# thick.net
KiCad netlist of a schematic drawn in EAGLE
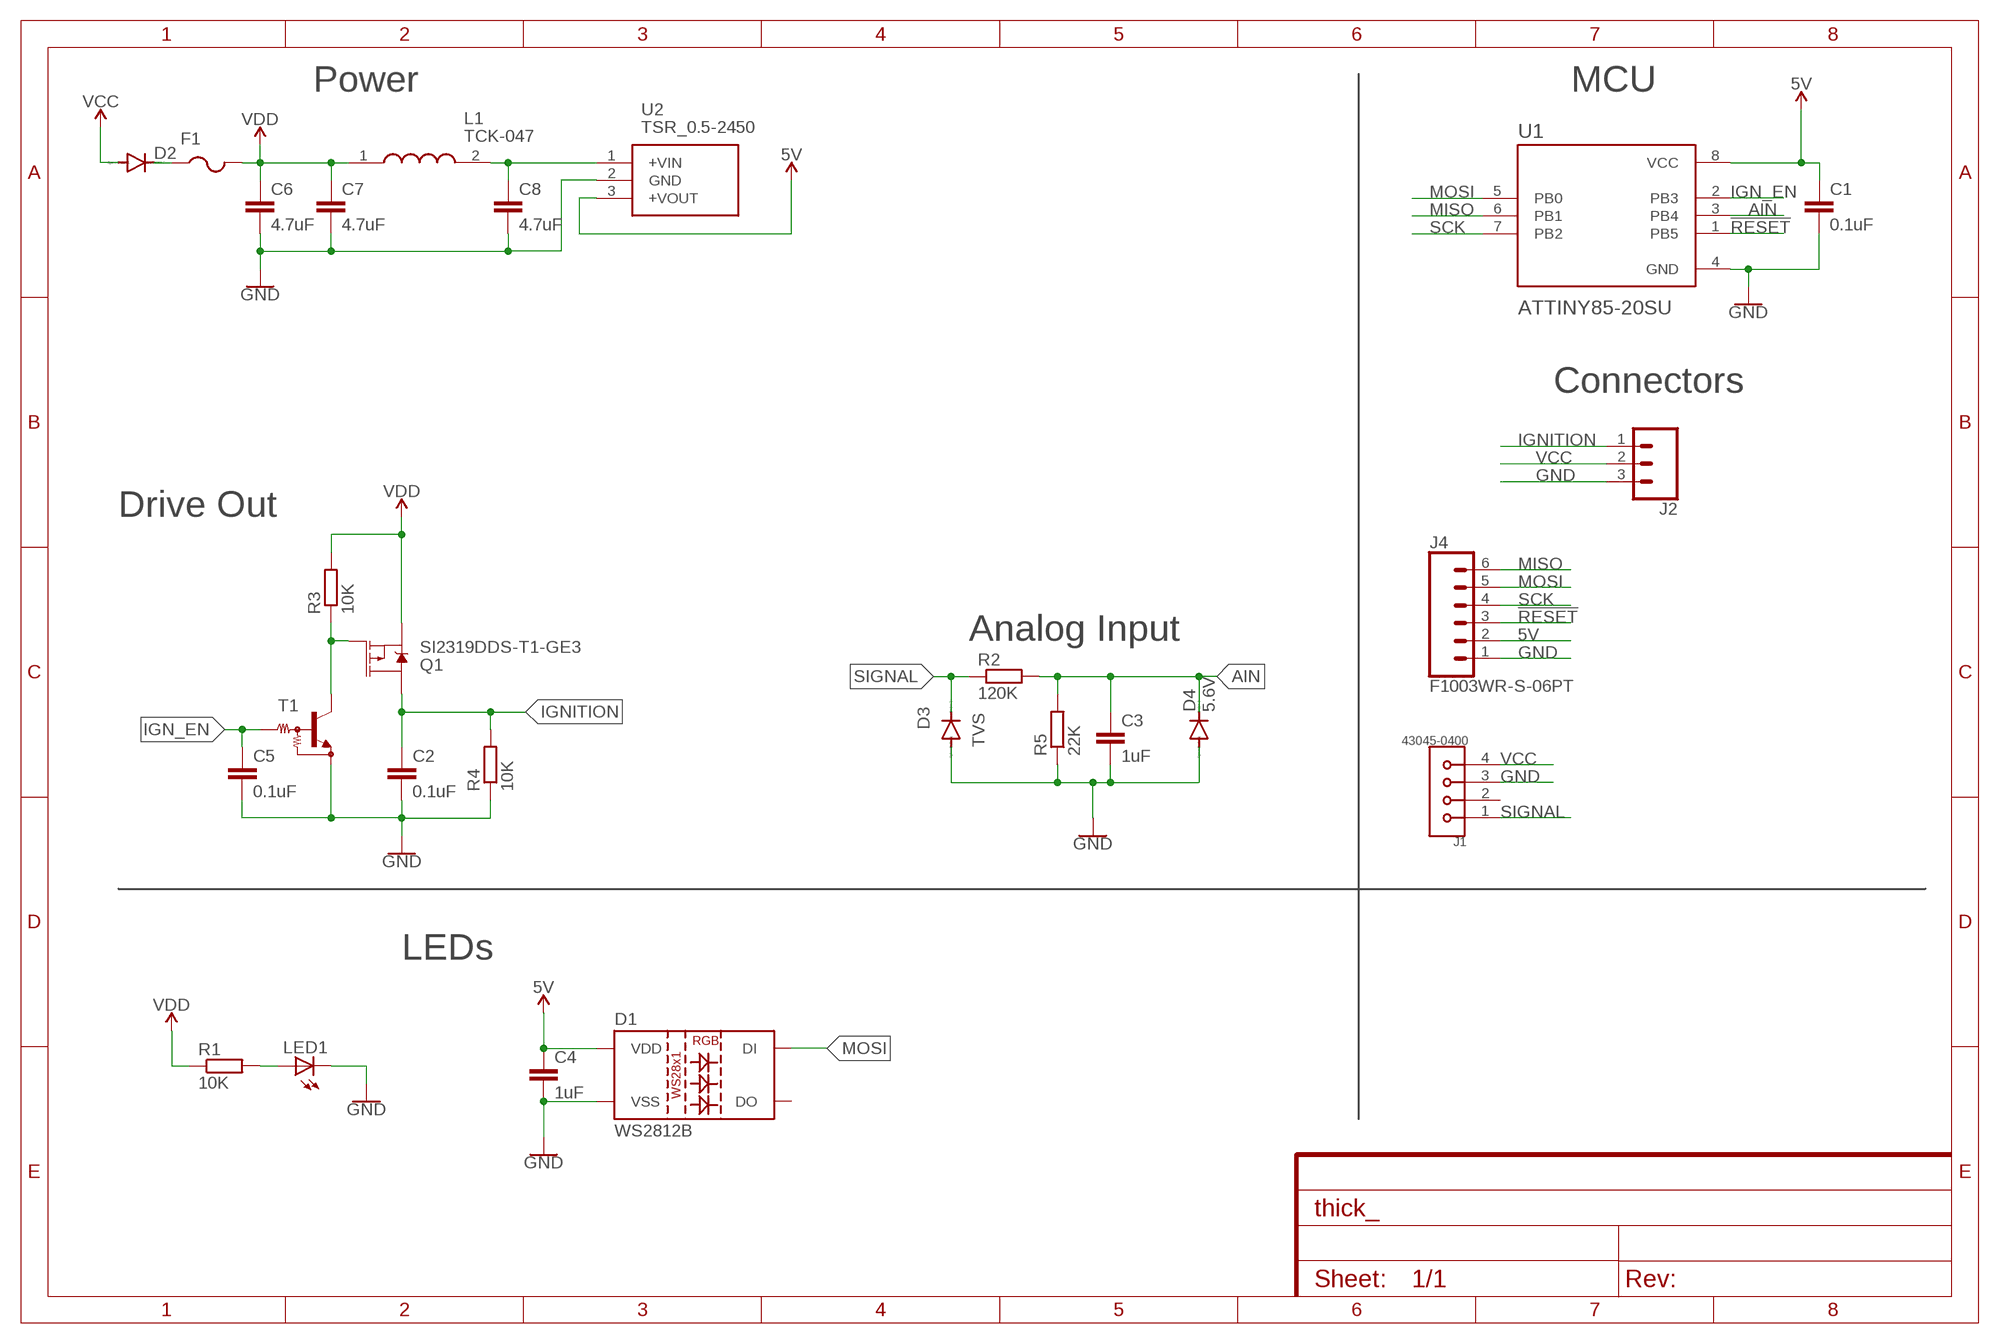
[diagram p0: schematic, sheet 1]

(export (version "E")
  (design (tool "Eeschema 10.0.6"))
  (components
    (comp (ref "C1")
      (value "0.1uF")
      (footprint "eagle-import:C0603")
      (libsource (lib "eagle-import") (part "C-EUC0603"))
    )
    (comp (ref "C2")
      (value "0.1uF")
      (footprint "eagle-import:C0603")
      (libsource (lib "eagle-import") (part "C-EUC0603"))
    )
    (comp (ref "C3")
      (value "1uF")
      (footprint "eagle-import:C0603")
      (libsource (lib "eagle-import") (part "C-EUC0603"))
    )
    (comp (ref "C4")
      (value "1uF")
      (footprint "eagle-import:C0603")
      (libsource (lib "eagle-import") (part "C-EUC0603"))
    )
    (comp (ref "C5")
      (value "0.1uF")
      (footprint "eagle-import:C0603")
      (libsource (lib "eagle-import") (part "C-EUC0603"))
    )
    (comp (ref "C6")
      (value "4.7uF")
      (footprint "eagle-import:C1206")
      (libsource (lib "eagle-import") (part "C-EUC1206"))
    )
    (comp (ref "C7")
      (value "4.7uF")
      (footprint "eagle-import:C1206")
      (libsource (lib "eagle-import") (part "C-EUC1206"))
    )
    (comp (ref "C8")
      (value "4.7uF")
      (footprint "eagle-import:C1206")
      (libsource (lib "eagle-import") (part "C-EUC1206"))
    )
    (comp (ref "D1")
      (value "WS2812B")
      (footprint "eagle-import:WS2812B")
      (libsource (lib "eagle-import") (part "WS2812B"))
    )
    (comp (ref "D2")
      (value "DIODE-MINIMELF")
      (footprint "eagle-import:MINIMELF")
      (libsource (lib "eagle-import") (part "DIODE-MINIMELF"))
    )
    (comp (ref "D3")
      (value "TVS")
      (footprint "eagle-import:DO214AC")
      (libsource (lib "eagle-import") (part "DIODE-DO214AC"))
    )
    (comp (ref "D4")
      (value "5.6V")
      (footprint "eagle-import:MINIMELF")
      (libsource (lib "eagle-import") (part "DIODE-MINIMELF"))
    )
    (comp (ref "F1")
      (value "PTCFUSE-1206")
      (footprint "eagle-import:R1206")
      (libsource (lib "eagle-import") (part "PTCFUSE-1206"))
    )
    (comp (ref "J1")
      (value "43045-0400")
      (footprint "eagle-import:MOLEX_43045-0400")
      (fields (field (name "MF") "Molex"))
      (libsource (lib "eagle-import") (part "43045-0400"))
    )
    (comp (ref "J2")
      (value "CONN_03LONGPADS")
      (footprint "eagle-import:1X03_LONGPADS")
      (libsource (lib "eagle-import") (part "CONN_03LONGPADS"))
    )
    (comp (ref "J4")
      (value "F1003WR-S-06PT")
      (footprint "eagle-import:1X06-1MM")
      (libsource (lib "eagle-import") (part "F1003WR-S-06PT"))
    )
    (comp (ref "L1")
      (value "TCK-047")
      (footprint "eagle-import:TCK047")
      (fields (field (name "MOUSER_PART_NUMBER") "495-TCK-047"))
      (libsource (lib "eagle-import") (part "TCK-047"))
    )
    (comp (ref "LED1")
      (value "LEDCHIPLED_0805")
      (footprint "eagle-import:CHIPLED_0805")
      (libsource (lib "eagle-import") (part "LEDCHIPLED_0805"))
    )
    (comp (ref "Q1")
      (value "SI2319DDS-T1-GE3")
      (footprint "eagle-import:SOT23-3")
      (libsource (lib "eagle-import") (part "MOSFET_PCH-DMG2307L"))
    )
    (comp (ref "R1")
      (value "10K")
      (footprint "eagle-import:R0603")
      (libsource (lib "eagle-import") (part "R-EU_R0603"))
    )
    (comp (ref "R2")
      (value "120K")
      (footprint "eagle-import:R0603")
      (libsource (lib "eagle-import") (part "R-EU_R0603"))
    )
    (comp (ref "R3")
      (value "10K")
      (footprint "eagle-import:R0603")
      (libsource (lib "eagle-import") (part "R-EU_R0603"))
    )
    (comp (ref "R4")
      (value "10K")
      (footprint "eagle-import:R0603")
      (libsource (lib "eagle-import") (part "R-EU_R0603"))
    )
    (comp (ref "R5")
      (value "22K")
      (footprint "eagle-import:R0603")
      (libsource (lib "eagle-import") (part "R-EU_R0603"))
    )
    (comp (ref "T1")
      (value "MUN2213T1-NPN_DRIVER-SC59-BEC")
      (footprint "eagle-import:SC59-BEC")
      (libsource (lib "eagle-import") (part "-NPN_DRIVER-SC59-BECMUN2213T1"))
    )
    (comp (ref "U1")
      (value "ATTINY85-20SU")
      (footprint "eagle-import:SOIC127P798X216-8N")
      (fields (field (name "MF") "Microchip Technology"))
      (libsource (lib "eagle-import") (part "ATTINY85-20SU"))
    )
    (comp (ref "U2")
      (value "TSR_0.5-2450")
      (footprint "eagle-import:TSR-0.5-2433")
      (fields
        (field (name "MANUFACTURER_PART_NUMBER") "TSR 0.5-2450")
        (field (name "MOUSER_PART_NUMBER") "495-TSR0.5-2450")
      )
      (libsource (lib "eagle-import") (part "TSR_0.5-2450"))
    )
  )
  (nets
    (net (code "1") (name "/MISO") (class "Default")
      (node (ref "J4") (pin "6") (pinfunction "6_6") (pintype "passive"))
      (node (ref "U1") (pin "6") (pinfunction "PB1_6") (pintype "bidirectional"))
    )
    (net (code "2") (name "/SCK") (class "Default")
      (node (ref "J4") (pin "4") (pinfunction "4_4") (pintype "passive"))
      (node (ref "U1") (pin "7") (pinfunction "PB2_7") (pintype "bidirectional"))
    )
    (net (code "3") (name "/~{RESET}") (class "Default")
      (node (ref "J4") (pin "3") (pinfunction "3_3") (pintype "passive"))
      (node (ref "U1") (pin "1") (pinfunction "PB5_1") (pintype "bidirectional"))
    )
    (net (code "4") (name "5V") (class "Default")
      (node (ref "C1") (pin "1") (pinfunction "1_1") (pintype "passive"))
      (node (ref "C4") (pin "1") (pinfunction "1_1") (pintype "passive"))
      (node (ref "D1") (pin "1") (pinfunction "VDD_1") (pintype "bidirectional"))
      (node (ref "J4") (pin "2") (pinfunction "2_2") (pintype "passive"))
      (node (ref "U1") (pin "8") (pinfunction "VCC_8") (pintype "power_in"))
      (node (ref "U2") (pin "3") (pinfunction "+VOUT_3") (pintype "bidirectional"))
    )
    (net (code "5") (name "AIN") (class "Default")
      (node (ref "C3") (pin "1") (pinfunction "1_1") (pintype "passive"))
      (node (ref "D4") (pin "C") (pinfunction "C_C") (pintype "passive"))
      (node (ref "R2") (pin "2") (pinfunction "2_2") (pintype "passive"))
      (node (ref "R5") (pin "2") (pinfunction "2_2") (pintype "passive"))
      (node (ref "U1") (pin "3") (pinfunction "PB4_3") (pintype "bidirectional"))
    )
    (net (code "6") (name "GND") (class "Default")
      (node (ref "C1") (pin "2") (pinfunction "2_2") (pintype "passive"))
      (node (ref "C2") (pin "2") (pinfunction "2_2") (pintype "passive"))
      (node (ref "C3") (pin "2") (pinfunction "2_2") (pintype "passive"))
      (node (ref "C4") (pin "2") (pinfunction "2_2") (pintype "passive"))
      (node (ref "C5") (pin "2") (pinfunction "2_2") (pintype "passive"))
      (node (ref "C6") (pin "2") (pinfunction "2_2") (pintype "passive"))
      (node (ref "C7") (pin "2") (pinfunction "2_2") (pintype "passive"))
      (node (ref "C8") (pin "2") (pinfunction "2_2") (pintype "passive"))
      (node (ref "D1") (pin "3") (pinfunction "VSS_3") (pintype "bidirectional"))
      (node (ref "D3") (pin "A") (pinfunction "A_A") (pintype "passive"))
      (node (ref "D4") (pin "A") (pinfunction "A_A") (pintype "passive"))
      (node (ref "J1") (pin "3") (pinfunction "3_3") (pintype "passive"))
      (node (ref "J2") (pin "3") (pinfunction "3_3") (pintype "passive"))
      (node (ref "J4") (pin "1") (pinfunction "1_1") (pintype "passive"))
      (node (ref "LED1") (pin "C") (pinfunction "C_C") (pintype "passive"))
      (node (ref "R4") (pin "1") (pinfunction "1_1") (pintype "passive"))
      (node (ref "R5") (pin "1") (pinfunction "1_1") (pintype "passive"))
      (node (ref "T1") (pin "E") (pinfunction "E_E") (pintype "passive"))
      (node (ref "U1") (pin "4") (pinfunction "GND_4") (pintype "power_in"))
      (node (ref "U2") (pin "2") (pinfunction "GND_2") (pintype "bidirectional"))
    )
    (net (code "7") (name "IGNITION") (class "Default")
      (node (ref "C2") (pin "1") (pinfunction "1_1") (pintype "passive"))
      (node (ref "J2") (pin "1") (pinfunction "1_1") (pintype "passive"))
      (node (ref "Q1") (pin "3") (pinfunction "D_3") (pintype "bidirectional"))
      (node (ref "R4") (pin "2") (pinfunction "2_2") (pintype "passive"))
    )
    (net (code "8") (name "IGN_EN") (class "Default")
      (node (ref "C5") (pin "1") (pinfunction "1_1") (pintype "passive"))
      (node (ref "T1") (pin "B") (pinfunction "B_B") (pintype "passive"))
      (node (ref "U1") (pin "2") (pinfunction "PB3_2") (pintype "bidirectional"))
    )
    (net (code "9") (name "MOSI") (class "Default")
      (node (ref "D1") (pin "4") (pinfunction "DI_4") (pintype "bidirectional"))
      (node (ref "J4") (pin "5") (pinfunction "5_5") (pintype "passive"))
      (node (ref "U1") (pin "5") (pinfunction "PB0_5") (pintype "bidirectional"))
    )
    (net (code "10") (name "Net-(D2-PadC)") (class "Default")
      (node (ref "D2") (pin "C") (pinfunction "C_C") (pintype "passive"))
      (node (ref "F1") (pin "1") (pinfunction "1_1") (pintype "passive"))
    )
    (net (code "11") (name "Net-(LED1-PadA)") (class "Default")
      (node (ref "LED1") (pin "A") (pinfunction "A_A") (pintype "passive"))
      (node (ref "R1") (pin "2") (pinfunction "2_2") (pintype "passive"))
    )
    (net (code "12") (name "Net-(Q1-G)") (class "Default")
      (node (ref "Q1") (pin "1") (pinfunction "G_1") (pintype "bidirectional"))
      (node (ref "R3") (pin "1") (pinfunction "1_1") (pintype "passive"))
      (node (ref "T1") (pin "C") (pinfunction "C_C") (pintype "passive"))
    )
    (net (code "13") (name "Net-(U2-+VIN)") (class "Default")
      (node (ref "C8") (pin "1") (pinfunction "1_1") (pintype "passive"))
      (node (ref "L1") (pin "2") (pinfunction "2_2") (pintype "bidirectional"))
      (node (ref "U2") (pin "1") (pinfunction "+VIN_1") (pintype "bidirectional"))
    )
    (net (code "14") (name "SIGNAL") (class "Default")
      (node (ref "D3") (pin "C") (pinfunction "C_C") (pintype "passive"))
      (node (ref "J1") (pin "1") (pinfunction "1_1") (pintype "passive"))
      (node (ref "R2") (pin "1") (pinfunction "1_1") (pintype "passive"))
    )
    (net (code "15") (name "VCC") (class "Default")
      (node (ref "D2") (pin "A") (pinfunction "A_A") (pintype "passive"))
      (node (ref "J1") (pin "4") (pinfunction "4_4") (pintype "passive"))
      (node (ref "J2") (pin "2") (pinfunction "2_2") (pintype "passive"))
    )
    (net (code "16") (name "VDD") (class "Default")
      (node (ref "C6") (pin "1") (pinfunction "1_1") (pintype "passive"))
      (node (ref "C7") (pin "1") (pinfunction "1_1") (pintype "passive"))
      (node (ref "F1") (pin "2") (pinfunction "2_2") (pintype "passive"))
      (node (ref "L1") (pin "1") (pinfunction "1_1") (pintype "bidirectional"))
      (node (ref "Q1") (pin "2") (pinfunction "S_2") (pintype "bidirectional"))
      (node (ref "R1") (pin "1") (pinfunction "1_1") (pintype "passive"))
      (node (ref "R3") (pin "2") (pinfunction "2_2") (pintype "passive"))
    )
    (net (code "17") (name "unconnected-(D1-DO-Pad2)") (class "Default")
      (node (ref "D1") (pin "2") (pinfunction "DO_2") (pintype "bidirectional"))
    )
    (net (code "18") (name "unconnected-(J1-Pad2)") (class "Default")
      (node (ref "J1") (pin "2") (pinfunction "2_2") (pintype "passive"))
    )
  )
)
